# strobe.net
KiCad netlist of a schematic drawn in EAGLE
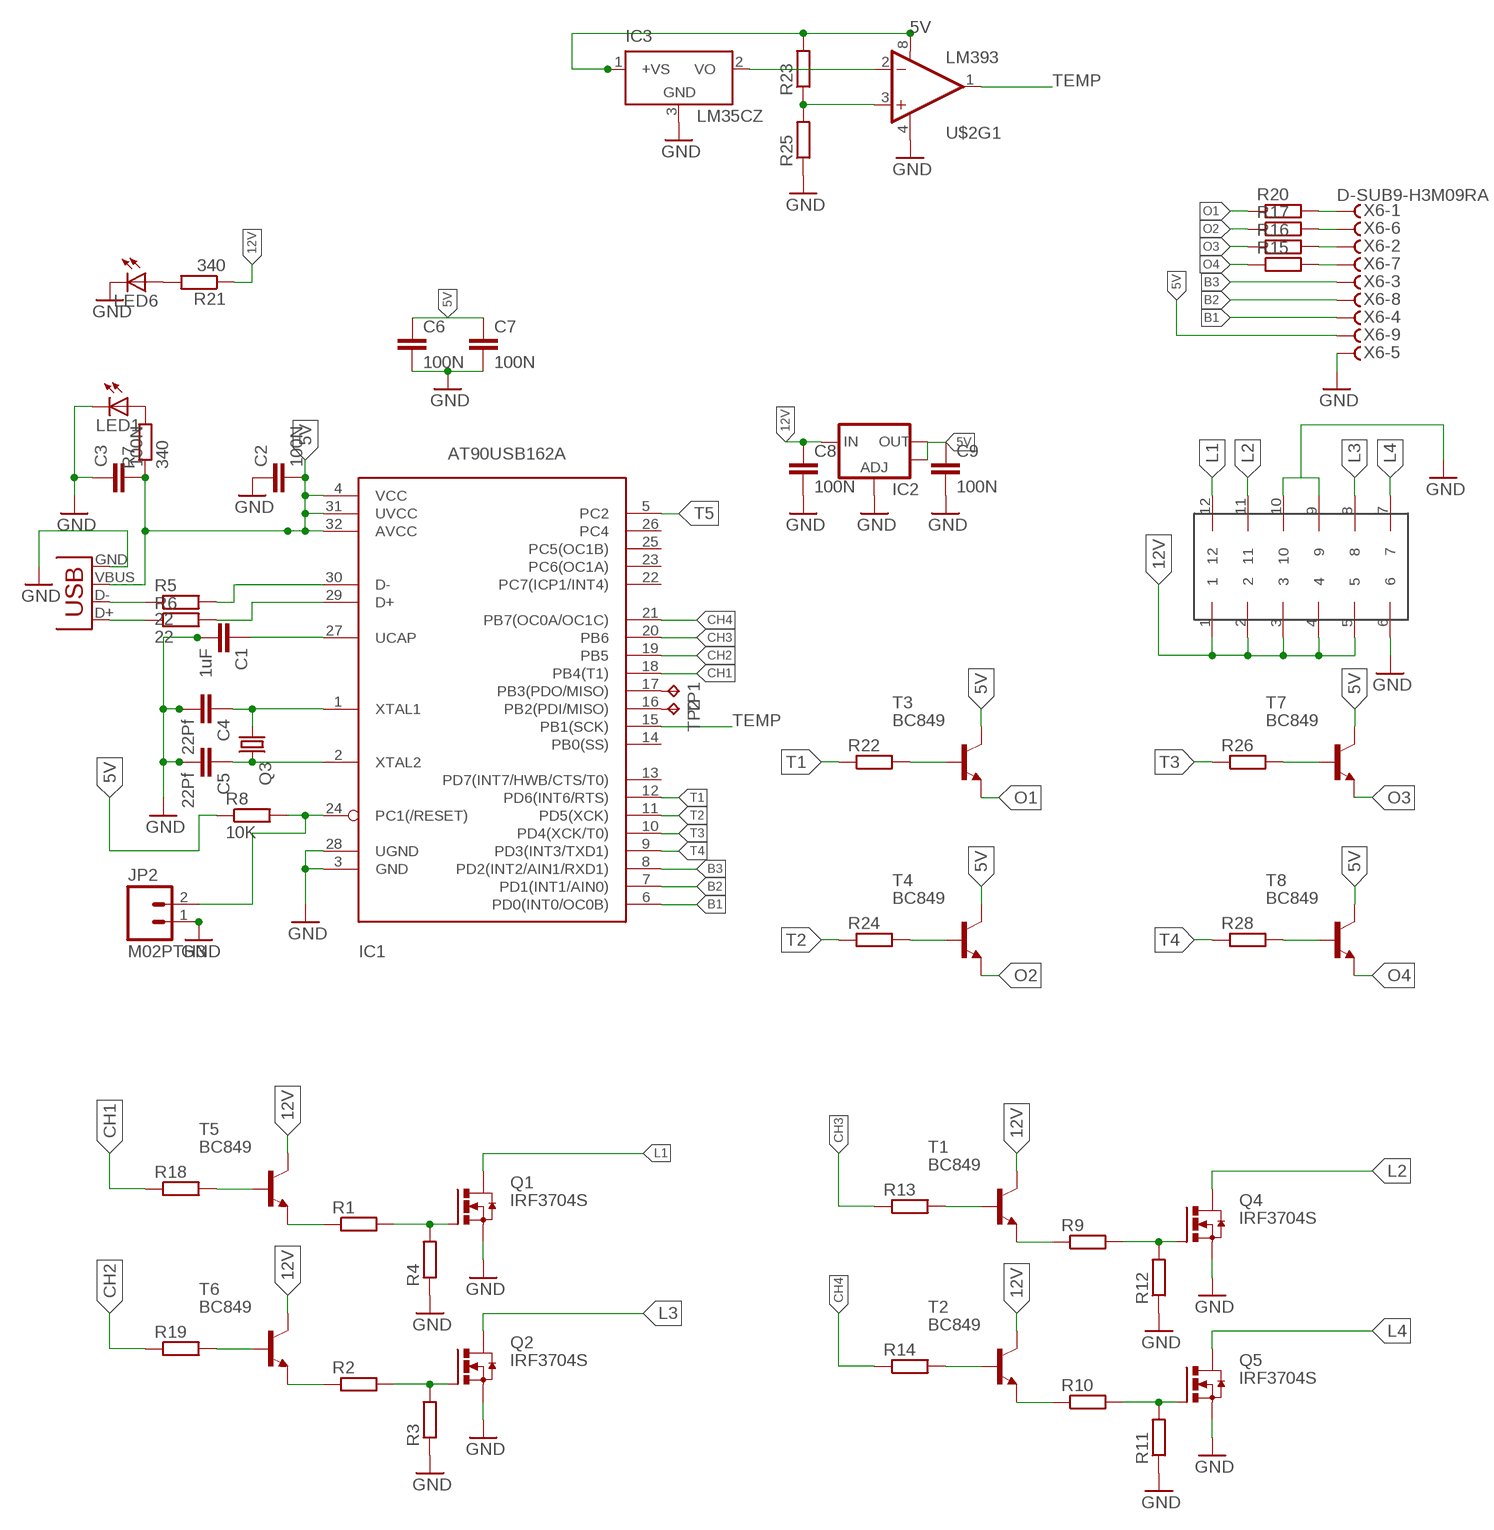
[diagram p0: schematic, sheet 1]

(export (version "E")
  (design (tool "Eeschema 10.0.6"))
  (components
    (comp (ref "C1")
      (value "1uF")
      (footprint "eagle-import:C0805")
      (libsource (lib "eagle-import") (part "C-EUC0805"))
    )
    (comp (ref "C2")
      (value "100N")
      (footprint "eagle-import:C0805")
      (libsource (lib "eagle-import") (part "C-EUC0805"))
    )
    (comp (ref "C3")
      (value "100N")
      (footprint "eagle-import:C0805")
      (libsource (lib "eagle-import") (part "C-EUC0805"))
    )
    (comp (ref "C4")
      (value "22Pf")
      (footprint "eagle-import:C0603")
      (libsource (lib "eagle-import") (part "C-EUC0603"))
    )
    (comp (ref "C5")
      (value "22Pf")
      (footprint "eagle-import:C0603")
      (libsource (lib "eagle-import") (part "C-EUC0603"))
    )
    (comp (ref "C6")
      (value "100N")
      (footprint "eagle-import:C0805")
      (libsource (lib "eagle-import") (part "C-EUC0805"))
    )
    (comp (ref "C7")
      (value "100N")
      (footprint "eagle-import:C0805")
      (libsource (lib "eagle-import") (part "C-EUC0805"))
    )
    (comp (ref "C8")
      (value "100N")
      (footprint "eagle-import:C0805")
      (libsource (lib "eagle-import") (part "C-EUC0805"))
    )
    (comp (ref "C9")
      (value "100N")
      (footprint "eagle-import:C0805")
      (libsource (lib "eagle-import") (part "C-EUC0805"))
    )
    (comp (ref "IC1")
      (value "AT90USB162A")
      (footprint "eagle-import:TQFP32-08")
      (libsource (lib "eagle-import") (part "AT90USB162A"))
    )
    (comp (ref "IC2")
      (value "V_REG_LM1117SOT223")
      (footprint "eagle-import:SOT223")
      (libsource (lib "eagle-import") (part "V_REG_LM1117SOT223"))
    )
    (comp (ref "IC3")
      (value "LM35CZ")
      (footprint "eagle-import:TO92")
      (libsource (lib "eagle-import") (part "LM35CZ"))
    )
    (comp (ref "JP1")
      (value "USB-B")
      (footprint "eagle-import:USB-B-PTH")
      (libsource (lib "eagle-import") (part "USBPTH"))
    )
    (comp (ref "JP2")
      (value "M02PTH3")
      (footprint "eagle-import:1X02_LONGPADS")
      (libsource (lib "eagle-import") (part "M02PTH3"))
    )
    (comp (ref "LED1")
      (value "LEDSML0805")
      (footprint "eagle-import:SML0805")
      (libsource (lib "eagle-import") (part "LEDSML0805"))
    )
    (comp (ref "LED6")
      (value "LEDSML0805")
      (footprint "eagle-import:SML0805")
      (libsource (lib "eagle-import") (part "LEDSML0805"))
    )
    (comp (ref "Q1")
      (value "IRF3704S")
      (footprint "eagle-import:D2PACK")
      (libsource (lib "eagle-import") (part "IRF3704S"))
    )
    (comp (ref "Q2")
      (value "IRF3704S")
      (footprint "eagle-import:D2PACK")
      (libsource (lib "eagle-import") (part "IRF3704S"))
    )
    (comp (ref "Q3")
      (value "CRYSTALSM49")
      (footprint "eagle-import:SM49")
      (libsource (lib "eagle-import") (part "CRYSTALSM49"))
    )
    (comp (ref "Q4")
      (value "IRF3704S")
      (footprint "eagle-import:D2PACK")
      (libsource (lib "eagle-import") (part "IRF3704S"))
    )
    (comp (ref "Q5")
      (value "IRF3704S")
      (footprint "eagle-import:D2PACK")
      (libsource (lib "eagle-import") (part "IRF3704S"))
    )
    (comp (ref "R1")
      (value "R-EU_R0805")
      (footprint "eagle-import:R0805")
      (libsource (lib "eagle-import") (part "R-EU_R0805"))
    )
    (comp (ref "R2")
      (value "R-EU_R0805")
      (footprint "eagle-import:R0805")
      (libsource (lib "eagle-import") (part "R-EU_R0805"))
    )
    (comp (ref "R3")
      (value "R-EU_R0805")
      (footprint "eagle-import:R0805")
      (libsource (lib "eagle-import") (part "R-EU_R0805"))
    )
    (comp (ref "R4")
      (value "R-EU_R0805")
      (footprint "eagle-import:R0805")
      (libsource (lib "eagle-import") (part "R-EU_R0805"))
    )
    (comp (ref "R5")
      (value "22")
      (footprint "eagle-import:R0805")
      (libsource (lib "eagle-import") (part "R-EU_R0805"))
    )
    (comp (ref "R6")
      (value "22")
      (footprint "eagle-import:R0805")
      (libsource (lib "eagle-import") (part "R-EU_R0805"))
    )
    (comp (ref "R7")
      (value "340")
      (footprint "eagle-import:R0805")
      (libsource (lib "eagle-import") (part "R-EU_R0805"))
    )
    (comp (ref "R8")
      (value "10K")
      (footprint "eagle-import:R0805")
      (libsource (lib "eagle-import") (part "R-EU_R0805"))
    )
    (comp (ref "R9")
      (value "R-EU_R0805")
      (footprint "eagle-import:R0805")
      (libsource (lib "eagle-import") (part "R-EU_R0805"))
    )
    (comp (ref "R10")
      (value "R-EU_R0805")
      (footprint "eagle-import:R0805")
      (libsource (lib "eagle-import") (part "R-EU_R0805"))
    )
    (comp (ref "R11")
      (value "R-EU_R0805")
      (footprint "eagle-import:R0805")
      (libsource (lib "eagle-import") (part "R-EU_R0805"))
    )
    (comp (ref "R12")
      (value "R-EU_R0805")
      (footprint "eagle-import:R0805")
      (libsource (lib "eagle-import") (part "R-EU_R0805"))
    )
    (comp (ref "R13")
      (value "R-EU_R0805")
      (footprint "eagle-import:R0805")
      (libsource (lib "eagle-import") (part "R-EU_R0805"))
    )
    (comp (ref "R14")
      (value "R-EU_R0805")
      (footprint "eagle-import:R0805")
      (libsource (lib "eagle-import") (part "R-EU_R0805"))
    )
    (comp (ref "R15")
      (value "R-EU_R0805")
      (footprint "eagle-import:R0805")
      (libsource (lib "eagle-import") (part "R-EU_R0805"))
    )
    (comp (ref "R16")
      (value "R-EU_R0805")
      (footprint "eagle-import:R0805")
      (libsource (lib "eagle-import") (part "R-EU_R0805"))
    )
    (comp (ref "R17")
      (value "R-EU_R0805")
      (footprint "eagle-import:R0805")
      (libsource (lib "eagle-import") (part "R-EU_R0805"))
    )
    (comp (ref "R18")
      (value "R-EU_R0805")
      (footprint "eagle-import:R0805")
      (libsource (lib "eagle-import") (part "R-EU_R0805"))
    )
    (comp (ref "R19")
      (value "R-EU_R0805")
      (footprint "eagle-import:R0805")
      (libsource (lib "eagle-import") (part "R-EU_R0805"))
    )
    (comp (ref "R20")
      (value "R-EU_R0805")
      (footprint "eagle-import:R0805")
      (libsource (lib "eagle-import") (part "R-EU_R0805"))
    )
    (comp (ref "R21")
      (value "340")
      (footprint "eagle-import:R0805")
      (libsource (lib "eagle-import") (part "R-EU_R0805"))
    )
    (comp (ref "R22")
      (value "R-EU_R0805")
      (footprint "eagle-import:R0805")
      (libsource (lib "eagle-import") (part "R-EU_R0805"))
    )
    (comp (ref "R23")
      (value "R-EU_M0805")
      (footprint "eagle-import:M0805")
      (libsource (lib "eagle-import") (part "R-EU_M0805"))
    )
    (comp (ref "R24")
      (value "R-EU_R0805")
      (footprint "eagle-import:R0805")
      (libsource (lib "eagle-import") (part "R-EU_R0805"))
    )
    (comp (ref "R25")
      (value "R-EU_M0805")
      (footprint "eagle-import:M0805")
      (libsource (lib "eagle-import") (part "R-EU_M0805"))
    )
    (comp (ref "R26")
      (value "R-EU_R0805")
      (footprint "eagle-import:R0805")
      (libsource (lib "eagle-import") (part "R-EU_R0805"))
    )
    (comp (ref "R28")
      (value "R-EU_R0805")
      (footprint "eagle-import:R0805")
      (libsource (lib "eagle-import") (part "R-EU_R0805"))
    )
    (comp (ref "T1")
      (value "BC849")
      (footprint "eagle-import:SOT23")
      (libsource (lib "eagle-import") (part "BC849"))
    )
    (comp (ref "T2")
      (value "BC849")
      (footprint "eagle-import:SOT23")
      (libsource (lib "eagle-import") (part "BC849"))
    )
    (comp (ref "T3")
      (value "BC849")
      (footprint "eagle-import:SOT23")
      (libsource (lib "eagle-import") (part "BC849"))
    )
    (comp (ref "T4")
      (value "BC849")
      (footprint "eagle-import:SOT23")
      (libsource (lib "eagle-import") (part "BC849"))
    )
    (comp (ref "T5")
      (value "BC849")
      (footprint "eagle-import:SOT23")
      (libsource (lib "eagle-import") (part "BC849"))
    )
    (comp (ref "T6")
      (value "BC849")
      (footprint "eagle-import:SOT23")
      (libsource (lib "eagle-import") (part "BC849"))
    )
    (comp (ref "T7")
      (value "BC849")
      (footprint "eagle-import:SOT23")
      (libsource (lib "eagle-import") (part "BC849"))
    )
    (comp (ref "T8")
      (value "BC849")
      (footprint "eagle-import:SOT23")
      (libsource (lib "eagle-import") (part "BC849"))
    )
    (comp (ref "TP1")
      (value "TPB1,27")
      (footprint "eagle-import:B1,27")
      (libsource (lib "eagle-import") (part "TPB1,27"))
    )
    (comp (ref "TP2")
      (value "TPB1,27")
      (footprint "eagle-import:B1,27")
      (libsource (lib "eagle-import") (part "TPB1,27"))
    )
    (comp (ref "U$1")
      (value "MF42-10")
      (footprint "eagle-import:MF42-10")
      (libsource (lib "eagle-import") (part "MF42-10"))
    )
    (comp (ref "U$2")
      (value "LM393")
      (footprint "eagle-import:SO08")
      (libsource (lib "eagle-import") (part "LM393"))
    )
    (comp (ref "X6")
      (value "D-SUB9-H3M09RA")
      (footprint "eagle-import:H3M09RA")
      (libsource (lib "eagle-import") (part "D-SUB9-H3M09RA"))
    )
  )
  (nets
    (net (code "1") (name "/TEMP") (class "Default")
      (node (ref "IC1") (pin "15") (pinfunction "PB1(SCK)_15") (pintype "bidirectional"))
      (node (ref "U$2") (pin "1") (pinfunction "OUT_1") (pintype "output"))
    )
    (net (code "2") (name "5V") (class "Default")
      (node (ref "C2") (pin "2") (pinfunction "2_2") (pintype "passive"))
      (node (ref "C3") (pin "2") (pinfunction "2_2") (pintype "passive"))
      (node (ref "C6") (pin "1") (pinfunction "1_1") (pintype "passive"))
      (node (ref "C7") (pin "1") (pinfunction "1_1") (pintype "passive"))
      (node (ref "C9") (pin "1") (pinfunction "1_1") (pintype "passive"))
      (node (ref "IC1") (pin "31") (pinfunction "UVCC_31") (pintype "bidirectional"))
      (node (ref "IC1") (pin "32") (pinfunction "AVCC_32") (pintype "bidirectional"))
      (node (ref "IC1") (pin "4") (pinfunction "VCC_4") (pintype "bidirectional"))
      (node (ref "IC2") (pin "2") (pinfunction "OUT_2") (pintype "output"))
      (node (ref "IC2") (pin "4") (pinfunction "OUT_4") (pintype "output"))
      (node (ref "IC3") (pin "1") (pinfunction "+VS_1") (pintype "input"))
      (node (ref "JP1") (pin "VBUS") (pinfunction "VBUS_VBUS") (pintype "bidirectional"))
      (node (ref "R23") (pin "2") (pinfunction "2_2") (pintype "passive"))
      (node (ref "R7") (pin "1") (pinfunction "1_1") (pintype "passive"))
      (node (ref "R8") (pin "1") (pinfunction "1_1") (pintype "passive"))
      (node (ref "T3") (pin "3") (pinfunction "C_3") (pintype "passive"))
      (node (ref "T4") (pin "3") (pinfunction "C_3") (pintype "passive"))
      (node (ref "T7") (pin "3") (pinfunction "C_3") (pintype "passive"))
      (node (ref "T8") (pin "3") (pinfunction "C_3") (pintype "passive"))
      (node (ref "U$2") (pin "8") (pinfunction "V+_8") (pintype "power_in"))
      (node (ref "X6") (pin "9") (pinfunction "F_9") (pintype "passive"))
    )
    (net (code "3") (name "12V") (class "Default")
      (node (ref "C8") (pin "1") (pinfunction "1_1") (pintype "passive"))
      (node (ref "IC2") (pin "3") (pinfunction "IN_3") (pintype "input"))
      (node (ref "R21") (pin "1") (pinfunction "1_1") (pintype "passive"))
      (node (ref "T1") (pin "3") (pinfunction "C_3") (pintype "passive"))
      (node (ref "T2") (pin "3") (pinfunction "C_3") (pintype "passive"))
      (node (ref "T5") (pin "3") (pinfunction "C_3") (pintype "passive"))
      (node (ref "T6") (pin "3") (pinfunction "C_3") (pintype "passive"))
      (node (ref "U$1") (pin "1") (pinfunction "1_1") (pintype "bidirectional"))
      (node (ref "U$1") (pin "2") (pinfunction "2_2") (pintype "bidirectional"))
      (node (ref "U$1") (pin "3") (pinfunction "3_3") (pintype "bidirectional"))
      (node (ref "U$1") (pin "4") (pinfunction "4_4") (pintype "bidirectional"))
      (node (ref "U$1") (pin "5") (pinfunction "5_5") (pintype "bidirectional"))
    )
    (net (code "4") (name "B1") (class "Default")
      (node (ref "IC1") (pin "6") (pinfunction "PD0(INT0/OC0B)_6") (pintype "bidirectional"))
      (node (ref "X6") (pin "4") (pinfunction "F_4") (pintype "passive"))
    )
    (net (code "5") (name "B2") (class "Default")
      (node (ref "IC1") (pin "7") (pinfunction "PD1(INT1/AIN0)_7") (pintype "bidirectional"))
      (node (ref "X6") (pin "8") (pinfunction "F_8") (pintype "passive"))
    )
    (net (code "6") (name "B3") (class "Default")
      (node (ref "IC1") (pin "8") (pinfunction "PD2(INT2/AIN1/RXD1)_8") (pintype "bidirectional"))
      (node (ref "X6") (pin "3") (pinfunction "F_3") (pintype "passive"))
    )
    (net (code "7") (name "CH1") (class "Default")
      (node (ref "IC1") (pin "18") (pinfunction "PB4(T1)_18") (pintype "bidirectional"))
      (node (ref "R18") (pin "1") (pinfunction "1_1") (pintype "passive"))
    )
    (net (code "8") (name "CH2") (class "Default")
      (node (ref "IC1") (pin "19") (pinfunction "PB5_19") (pintype "bidirectional"))
      (node (ref "R19") (pin "1") (pinfunction "1_1") (pintype "passive"))
    )
    (net (code "9") (name "CH3") (class "Default")
      (node (ref "IC1") (pin "20") (pinfunction "PB6_20") (pintype "bidirectional"))
      (node (ref "R13") (pin "1") (pinfunction "1_1") (pintype "passive"))
    )
    (net (code "10") (name "CH4") (class "Default")
      (node (ref "IC1") (pin "21") (pinfunction "PB7(OC0A/OC1C)_21") (pintype "bidirectional"))
      (node (ref "R14") (pin "1") (pinfunction "1_1") (pintype "passive"))
    )
    (net (code "11") (name "GND") (class "Default")
      (node (ref "C1") (pin "2") (pinfunction "2_2") (pintype "passive"))
      (node (ref "C2") (pin "1") (pinfunction "1_1") (pintype "passive"))
      (node (ref "C3") (pin "1") (pinfunction "1_1") (pintype "passive"))
      (node (ref "C4") (pin "2") (pinfunction "2_2") (pintype "passive"))
      (node (ref "C5") (pin "2") (pinfunction "2_2") (pintype "passive"))
      (node (ref "C6") (pin "2") (pinfunction "2_2") (pintype "passive"))
      (node (ref "C7") (pin "2") (pinfunction "2_2") (pintype "passive"))
      (node (ref "C8") (pin "2") (pinfunction "2_2") (pintype "passive"))
      (node (ref "C9") (pin "2") (pinfunction "2_2") (pintype "passive"))
      (node (ref "IC1") (pin "28") (pinfunction "UGND_28") (pintype "bidirectional"))
      (node (ref "IC1") (pin "3") (pinfunction "GND_3") (pintype "bidirectional"))
      (node (ref "IC2") (pin "1") (pinfunction "ADJ_1") (pintype "input"))
      (node (ref "IC3") (pin "3") (pinfunction "GND_3") (pintype "power_in"))
      (node (ref "JP1") (pin "GND") (pinfunction "GND_GND") (pintype "bidirectional"))
      (node (ref "JP2") (pin "1") (pinfunction "1_1") (pintype "passive"))
      (node (ref "LED1") (pin "C") (pinfunction "C_C") (pintype "passive"))
      (node (ref "LED6") (pin "C") (pinfunction "C_C") (pintype "passive"))
      (node (ref "Q1") (pin "3") (pinfunction "S_3") (pintype "passive"))
      (node (ref "Q2") (pin "3") (pinfunction "S_3") (pintype "passive"))
      (node (ref "Q4") (pin "3") (pinfunction "S_3") (pintype "passive"))
      (node (ref "Q5") (pin "3") (pinfunction "S_3") (pintype "passive"))
      (node (ref "R11") (pin "1") (pinfunction "1_1") (pintype "passive"))
      (node (ref "R12") (pin "1") (pinfunction "1_1") (pintype "passive"))
      (node (ref "R25") (pin "1") (pinfunction "1_1") (pintype "passive"))
      (node (ref "R3") (pin "1") (pinfunction "1_1") (pintype "passive"))
      (node (ref "R4") (pin "1") (pinfunction "1_1") (pintype "passive"))
      (node (ref "U$1") (pin "10") (pinfunction "10_10") (pintype "bidirectional"))
      (node (ref "U$1") (pin "6") (pinfunction "6_6") (pintype "bidirectional"))
      (node (ref "U$1") (pin "9") (pinfunction "9_9") (pintype "bidirectional"))
      (node (ref "U$2") (pin "4") (pinfunction "V-_4") (pintype "power_in"))
      (node (ref "X6") (pin "5") (pinfunction "F_5") (pintype "passive"))
    )
    (net (code "12") (name "L1") (class "Default")
      (node (ref "Q1") (pin "2") (pinfunction "D_2") (pintype "passive"))
      (node (ref "U$1") (pin "12") (pinfunction "12_12") (pintype "bidirectional"))
    )
    (net (code "13") (name "L2") (class "Default")
      (node (ref "Q4") (pin "2") (pinfunction "D_2") (pintype "passive"))
      (node (ref "U$1") (pin "11") (pinfunction "11_11") (pintype "bidirectional"))
    )
    (net (code "14") (name "L3") (class "Default")
      (node (ref "Q2") (pin "2") (pinfunction "D_2") (pintype "passive"))
      (node (ref "U$1") (pin "8") (pinfunction "8_8") (pintype "bidirectional"))
    )
    (net (code "15") (name "L4") (class "Default")
      (node (ref "Q5") (pin "2") (pinfunction "D_2") (pintype "passive"))
      (node (ref "U$1") (pin "7") (pinfunction "7_7") (pintype "bidirectional"))
    )
    (net (code "16") (name "Net-(IC1-D+)") (class "Default")
      (node (ref "IC1") (pin "29") (pinfunction "D+_29") (pintype "bidirectional"))
      (node (ref "R6") (pin "2") (pinfunction "2_2") (pintype "passive"))
    )
    (net (code "17") (name "Net-(IC1-D-)") (class "Default")
      (node (ref "IC1") (pin "30") (pinfunction "D-_30") (pintype "bidirectional"))
      (node (ref "R5") (pin "2") (pinfunction "2_2") (pintype "passive"))
    )
    (net (code "18") (name "Net-(IC1-PB2(PDI{slash}MISO))") (class "Default")
      (node (ref "IC1") (pin "16") (pinfunction "PB2(PDI/MISO)_16") (pintype "bidirectional"))
      (node (ref "TP2") (pin "TP") (pinfunction "TP_TP") (pintype "input"))
    )
    (net (code "19") (name "Net-(IC1-PB3(PDO{slash}MISO))") (class "Default")
      (node (ref "IC1") (pin "17") (pinfunction "PB3(PDO/MISO)_17") (pintype "bidirectional"))
      (node (ref "TP1") (pin "TP") (pinfunction "TP_TP") (pintype "input"))
    )
    (net (code "20") (name "Net-(IC1-PC1({slash}RESET))") (class "Default")
      (node (ref "IC1") (pin "24") (pinfunction "PC1(/RESET)_24") (pintype "bidirectional"))
      (node (ref "JP2") (pin "2") (pinfunction "2_2") (pintype "passive"))
      (node (ref "R8") (pin "2") (pinfunction "2_2") (pintype "passive"))
    )
    (net (code "21") (name "Net-(IC1-UCAP)") (class "Default")
      (node (ref "C1") (pin "1") (pinfunction "1_1") (pintype "passive"))
      (node (ref "IC1") (pin "27") (pinfunction "UCAP_27") (pintype "bidirectional"))
    )
    (net (code "22") (name "Net-(IC1-XTAL1)") (class "Default")
      (node (ref "C4") (pin "1") (pinfunction "1_1") (pintype "passive"))
      (node (ref "IC1") (pin "1") (pinfunction "XTAL1_1") (pintype "bidirectional"))
      (node (ref "Q3") (pin "1") (pinfunction "1_1") (pintype "passive"))
    )
    (net (code "23") (name "Net-(IC1-XTAL2)") (class "Default")
      (node (ref "C5") (pin "1") (pinfunction "1_1") (pintype "passive"))
      (node (ref "IC1") (pin "2") (pinfunction "XTAL2_2") (pintype "bidirectional"))
      (node (ref "Q3") (pin "2") (pinfunction "2_2") (pintype "passive"))
    )
    (net (code "24") (name "Net-(IC3-VO)") (class "Default")
      (node (ref "IC3") (pin "2") (pinfunction "VO_2") (pintype "input"))
      (node (ref "U$2") (pin "2") (pinfunction "-IN_2") (pintype "input"))
    )
    (net (code "25") (name "Net-(JP1-PadD+)") (class "Default")
      (node (ref "JP1") (pin "D+") (pinfunction "D+_D+") (pintype "bidirectional"))
      (node (ref "R6") (pin "1") (pinfunction "1_1") (pintype "passive"))
    )
    (net (code "26") (name "Net-(JP1-PadD-)") (class "Default")
      (node (ref "JP1") (pin "D-") (pinfunction "D-_D-") (pintype "bidirectional"))
      (node (ref "R5") (pin "1") (pinfunction "1_1") (pintype "passive"))
    )
    (net (code "27") (name "Net-(LED1-PadA)") (class "Default")
      (node (ref "LED1") (pin "A") (pinfunction "A_A") (pintype "passive"))
      (node (ref "R7") (pin "2") (pinfunction "2_2") (pintype "passive"))
    )
    (net (code "28") (name "Net-(LED6-PadA)") (class "Default")
      (node (ref "LED6") (pin "A") (pinfunction "A_A") (pintype "passive"))
      (node (ref "R21") (pin "2") (pinfunction "2_2") (pintype "passive"))
    )
    (net (code "29") (name "Net-(Q1-G)") (class "Default")
      (node (ref "Q1") (pin "1") (pinfunction "G_1") (pintype "passive"))
      (node (ref "R1") (pin "2") (pinfunction "2_2") (pintype "passive"))
      (node (ref "R4") (pin "2") (pinfunction "2_2") (pintype "passive"))
    )
    (net (code "30") (name "Net-(Q2-G)") (class "Default")
      (node (ref "Q2") (pin "1") (pinfunction "G_1") (pintype "passive"))
      (node (ref "R2") (pin "2") (pinfunction "2_2") (pintype "passive"))
      (node (ref "R3") (pin "2") (pinfunction "2_2") (pintype "passive"))
    )
    (net (code "31") (name "Net-(Q4-G)") (class "Default")
      (node (ref "Q4") (pin "1") (pinfunction "G_1") (pintype "passive"))
      (node (ref "R12") (pin "2") (pinfunction "2_2") (pintype "passive"))
      (node (ref "R9") (pin "2") (pinfunction "2_2") (pintype "passive"))
    )
    (net (code "32") (name "Net-(Q5-G)") (class "Default")
      (node (ref "Q5") (pin "1") (pinfunction "G_1") (pintype "passive"))
      (node (ref "R10") (pin "2") (pinfunction "2_2") (pintype "passive"))
      (node (ref "R11") (pin "2") (pinfunction "2_2") (pintype "passive"))
    )
    (net (code "33") (name "Net-(T1-B)") (class "Default")
      (node (ref "R13") (pin "2") (pinfunction "2_2") (pintype "passive"))
      (node (ref "T1") (pin "1") (pinfunction "B_1") (pintype "passive"))
    )
    (net (code "34") (name "Net-(T1-E)") (class "Default")
      (node (ref "R9") (pin "1") (pinfunction "1_1") (pintype "passive"))
      (node (ref "T1") (pin "2") (pinfunction "E_2") (pintype "passive"))
    )
    (net (code "35") (name "Net-(T2-B)") (class "Default")
      (node (ref "R14") (pin "2") (pinfunction "2_2") (pintype "passive"))
      (node (ref "T2") (pin "1") (pinfunction "B_1") (pintype "passive"))
    )
    (net (code "36") (name "Net-(T2-E)") (class "Default")
      (node (ref "R10") (pin "1") (pinfunction "1_1") (pintype "passive"))
      (node (ref "T2") (pin "2") (pinfunction "E_2") (pintype "passive"))
    )
    (net (code "37") (name "Net-(T3-B)") (class "Default")
      (node (ref "R22") (pin "2") (pinfunction "2_2") (pintype "passive"))
      (node (ref "T3") (pin "1") (pinfunction "B_1") (pintype "passive"))
    )
    (net (code "38") (name "Net-(T4-B)") (class "Default")
      (node (ref "R24") (pin "2") (pinfunction "2_2") (pintype "passive"))
      (node (ref "T4") (pin "1") (pinfunction "B_1") (pintype "passive"))
    )
    (net (code "39") (name "Net-(T5-B)") (class "Default")
      (node (ref "R18") (pin "2") (pinfunction "2_2") (pintype "passive"))
      (node (ref "T5") (pin "1") (pinfunction "B_1") (pintype "passive"))
    )
    (net (code "40") (name "Net-(T5-E)") (class "Default")
      (node (ref "R1") (pin "1") (pinfunction "1_1") (pintype "passive"))
      (node (ref "T5") (pin "2") (pinfunction "E_2") (pintype "passive"))
    )
    (net (code "41") (name "Net-(T6-B)") (class "Default")
      (node (ref "R19") (pin "2") (pinfunction "2_2") (pintype "passive"))
      (node (ref "T6") (pin "1") (pinfunction "B_1") (pintype "passive"))
    )
    (net (code "42") (name "Net-(T6-E)") (class "Default")
      (node (ref "R2") (pin "1") (pinfunction "1_1") (pintype "passive"))
      (node (ref "T6") (pin "2") (pinfunction "E_2") (pintype "passive"))
    )
    (net (code "43") (name "Net-(T7-B)") (class "Default")
      (node (ref "R26") (pin "2") (pinfunction "2_2") (pintype "passive"))
      (node (ref "T7") (pin "1") (pinfunction "B_1") (pintype "passive"))
    )
    (net (code "44") (name "Net-(T8-B)") (class "Default")
      (node (ref "R28") (pin "2") (pinfunction "2_2") (pintype "passive"))
      (node (ref "T8") (pin "1") (pinfunction "B_1") (pintype "passive"))
    )
    (net (code "45") (name "Net-(U$2A-+IN)") (class "Default")
      (node (ref "R23") (pin "1") (pinfunction "1_1") (pintype "passive"))
      (node (ref "R25") (pin "2") (pinfunction "2_2") (pintype "passive"))
      (node (ref "U$2") (pin "3") (pinfunction "+IN_3") (pintype "input"))
    )
    (net (code "46") (name "Net-(X6A-F)") (class "Default")
      (node (ref "R20") (pin "2") (pinfunction "2_2") (pintype "passive"))
      (node (ref "X6") (pin "1") (pinfunction "F_1") (pintype "passive"))
    )
    (net (code "47") (name "Net-(X6B-F)") (class "Default")
      (node (ref "R16") (pin "2") (pinfunction "2_2") (pintype "passive"))
      (node (ref "X6") (pin "2") (pinfunction "F_2") (pintype "passive"))
    )
    (net (code "48") (name "Net-(X6F-F)") (class "Default")
      (node (ref "R17") (pin "2") (pinfunction "2_2") (pintype "passive"))
      (node (ref "X6") (pin "6") (pinfunction "F_6") (pintype "passive"))
    )
    (net (code "49") (name "Net-(X6G-F)") (class "Default")
      (node (ref "R15") (pin "2") (pinfunction "2_2") (pintype "passive"))
      (node (ref "X6") (pin "7") (pinfunction "F_7") (pintype "passive"))
    )
    (net (code "50") (name "O1") (class "Default")
      (node (ref "R20") (pin "1") (pinfunction "1_1") (pintype "passive"))
      (node (ref "T3") (pin "2") (pinfunction "E_2") (pintype "passive"))
    )
    (net (code "51") (name "O2") (class "Default")
      (node (ref "R17") (pin "1") (pinfunction "1_1") (pintype "passive"))
      (node (ref "T4") (pin "2") (pinfunction "E_2") (pintype "passive"))
    )
    (net (code "52") (name "O3") (class "Default")
      (node (ref "R16") (pin "1") (pinfunction "1_1") (pintype "passive"))
      (node (ref "T7") (pin "2") (pinfunction "E_2") (pintype "passive"))
    )
    (net (code "53") (name "O4") (class "Default")
      (node (ref "R15") (pin "1") (pinfunction "1_1") (pintype "passive"))
      (node (ref "T8") (pin "2") (pinfunction "E_2") (pintype "passive"))
    )
    (net (code "54") (name "T1") (class "Default")
      (node (ref "IC1") (pin "12") (pinfunction "PD6(INT6/RTS)_12") (pintype "bidirectional"))
      (node (ref "R22") (pin "1") (pinfunction "1_1") (pintype "passive"))
    )
    (net (code "55") (name "T2") (class "Default")
      (node (ref "IC1") (pin "11") (pinfunction "PD5(XCK)_11") (pintype "bidirectional"))
      (node (ref "R24") (pin "1") (pinfunction "1_1") (pintype "passive"))
    )
    (net (code "56") (name "T3") (class "Default")
      (node (ref "IC1") (pin "10") (pinfunction "PD4(XCK/T0)_10") (pintype "bidirectional"))
      (node (ref "R26") (pin "1") (pinfunction "1_1") (pintype "passive"))
    )
    (net (code "57") (name "T4") (class "Default")
      (node (ref "IC1") (pin "9") (pinfunction "PD3(INT3/TXD1)_9") (pintype "bidirectional"))
      (node (ref "R28") (pin "1") (pinfunction "1_1") (pintype "passive"))
    )
    (net (code "58") (name "T5") (class "Default")
      (node (ref "IC1") (pin "5") (pinfunction "PC2_5") (pintype "bidirectional"))
    )
    (net (code "59") (name "unconnected-(IC1-PB0(SS)-Pad14)") (class "Default")
      (node (ref "IC1") (pin "14") (pinfunction "PB0(SS)_14") (pintype "bidirectional"))
    )
    (net (code "60") (name "unconnected-(IC1-PC4-Pad26)") (class "Default")
      (node (ref "IC1") (pin "26") (pinfunction "PC4_26") (pintype "bidirectional"))
    )
    (net (code "61") (name "unconnected-(IC1-PC5(OC1B)-Pad25)") (class "Default")
      (node (ref "IC1") (pin "25") (pinfunction "PC5(OC1B)_25") (pintype "bidirectional"))
    )
    (net (code "62") (name "unconnected-(IC1-PC6(OC1A)-Pad23)") (class "Default")
      (node (ref "IC1") (pin "23") (pinfunction "PC6(OC1A)_23") (pintype "bidirectional"))
    )
    (net (code "63") (name "unconnected-(IC1-PC7(ICP1{slash}INT4)-Pad22)") (class "Default")
      (node (ref "IC1") (pin "22") (pinfunction "PC7(ICP1/INT4)_22") (pintype "bidirectional"))
    )
    (net (code "64") (name "unconnected-(IC1-PD7(INT7{slash}HWB{slash}CTS{slash}T0)-Pad13)") (class "Default")
      (node (ref "IC1") (pin "13") (pinfunction "PD7(INT7/HWB/CTS/T0)_13") (pintype "bidirectional"))
    )
  )
)
